# Top.net
KiCad netlist of a schematic drawn in Altium Designer
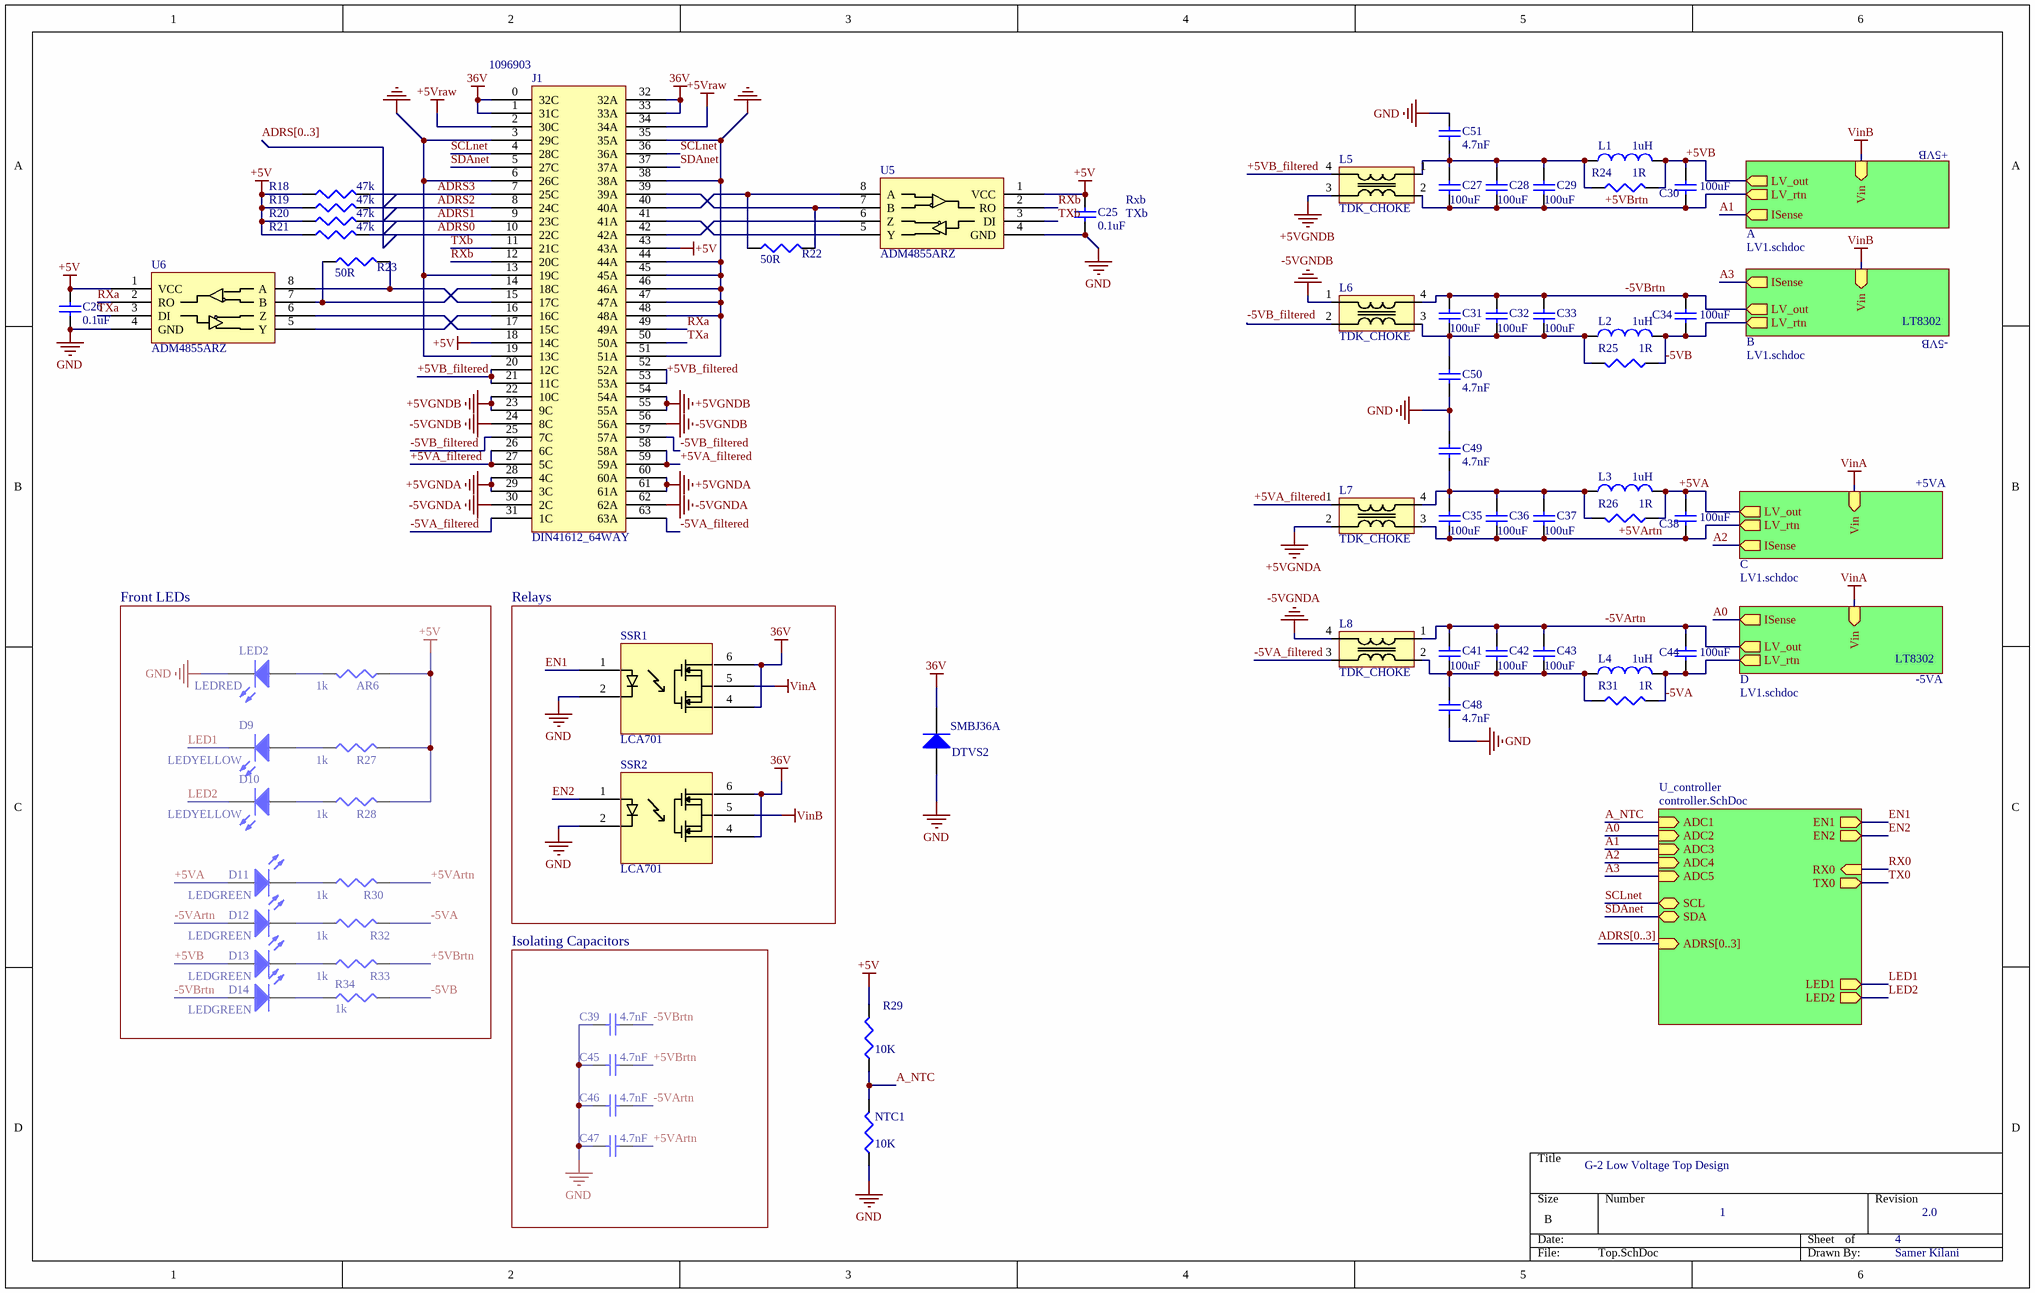
[diagram p0: Top.SchDoc]

(export (version "E")
  (design (tool "Eeschema 10.0.6"))
  (components
    (comp (ref "AR6")
      (value "1k")
      (footprint "J1-0603")
      (description "Resistor")
      (fields (field (name "PUBLISHER") "Altium Limited"))
      (libsource (lib "Miscellaneous Devices") (part "Res3"))
    )
    (comp (ref "C25")
      (value "0.1uF")
      (footprint "1608[0603]")
      (description "Capacitor (Semiconductor SIM Model)")
      (fields
        (field (name "PARTNO") "CC0603KRX7R9BB104")
        (field (name "Comment") "Cap Semi")
        (field (name "PUBLISHER") "Altium Limited")
      )
      (libsource (lib "Miscellaneous Devices") (part "Cap Semi"))
    )
    (comp (ref "C26")
      (value "0.1uF")
      (footprint "1608[0603]")
      (description "Capacitor (Semiconductor SIM Model)")
      (fields
        (field (name "PARTNO") "CC0603KRX7R9BB104")
        (field (name "Comment") "Cap Semi")
        (field (name "PUBLISHER") "Altium Limited")
      )
      (libsource (lib "Miscellaneous Devices") (part "Cap Semi"))
    )
    (comp (ref "C27")
      (value "100uF")
      (footprint "C1210")
      (description "Capacitor (Semiconductor SIM Model)")
      (fields
        (field (name "PARTNO") "CL32A107MPVNNNE")
        (field (name "Comment") "Cap Semi")
        (field (name "PUBLISHER") "Altium Limited")
      )
      (libsource (lib "Miscellaneous Devices") (part "Cap Semi"))
    )
    (comp (ref "C28")
      (value "100uF")
      (footprint "C1210")
      (description "Capacitor (Semiconductor SIM Model)")
      (fields
        (field (name "PARTNO") "CL32A107MPVNNNE")
        (field (name "Comment") "Cap Semi")
        (field (name "PUBLISHER") "Altium Limited")
      )
      (libsource (lib "Miscellaneous Devices") (part "Cap Semi"))
    )
    (comp (ref "C29")
      (value "100uF")
      (footprint "C1210")
      (description "Capacitor (Semiconductor SIM Model)")
      (fields
        (field (name "PARTNO") "CL32A107MPVNNNE")
        (field (name "Comment") "Cap Semi")
        (field (name "PUBLISHER") "Altium Limited")
      )
      (libsource (lib "Miscellaneous Devices") (part "Cap Semi"))
    )
    (comp (ref "C30")
      (value "100uF")
      (footprint "C1210")
      (description "Capacitor (Semiconductor SIM Model)")
      (fields
        (field (name "PARTNO") "C3225X5R0J107M250AC")
        (field (name "Comment") "Cap Semi")
        (field (name "PUBLISHER") "Altium Limited")
      )
      (libsource (lib "Miscellaneous Devices") (part "Cap Semi"))
    )
    (comp (ref "C31")
      (value "100uF")
      (footprint "C1210")
      (description "Capacitor (Semiconductor SIM Model)")
      (fields
        (field (name "PARTNO") "CL32A107MPVNNNE")
        (field (name "Comment") "Cap Semi")
        (field (name "PUBLISHER") "Altium Limited")
      )
      (libsource (lib "Miscellaneous Devices") (part "Cap Semi"))
    )
    (comp (ref "C32")
      (value "100uF")
      (footprint "C1210")
      (description "Capacitor (Semiconductor SIM Model)")
      (fields
        (field (name "PARTNO") "CL32A107MPVNNNE")
        (field (name "Comment") "Cap Semi")
        (field (name "PUBLISHER") "Altium Limited")
      )
      (libsource (lib "Miscellaneous Devices") (part "Cap Semi"))
    )
    (comp (ref "C33")
      (value "100uF")
      (footprint "C1210")
      (description "Capacitor (Semiconductor SIM Model)")
      (fields
        (field (name "PARTNO") "CL32A107MPVNNNE")
        (field (name "Comment") "Cap Semi")
        (field (name "PUBLISHER") "Altium Limited")
      )
      (libsource (lib "Miscellaneous Devices") (part "Cap Semi"))
    )
    (comp (ref "C34")
      (value "100uF")
      (footprint "C1210")
      (description "Capacitor (Semiconductor SIM Model)")
      (fields
        (field (name "PARTNO") "C3225X5R0J107M250AC")
        (field (name "Comment") "Cap Semi")
        (field (name "PUBLISHER") "Altium Limited")
      )
      (libsource (lib "Miscellaneous Devices") (part "Cap Semi"))
    )
    (comp (ref "C35")
      (value "100uF")
      (footprint "C1210")
      (description "Capacitor (Semiconductor SIM Model)")
      (fields
        (field (name "PARTNO") "CL32A107MPVNNNE")
        (field (name "Comment") "Cap Semi")
        (field (name "PUBLISHER") "Altium Limited")
      )
      (libsource (lib "Miscellaneous Devices") (part "Cap Semi"))
    )
    (comp (ref "C36")
      (value "100uF")
      (footprint "C1210")
      (description "Capacitor (Semiconductor SIM Model)")
      (fields
        (field (name "PARTNO") "CL32A107MPVNNNE")
        (field (name "Comment") "Cap Semi")
        (field (name "PUBLISHER") "Altium Limited")
      )
      (libsource (lib "Miscellaneous Devices") (part "Cap Semi"))
    )
    (comp (ref "C37")
      (value "100uF")
      (footprint "C1210")
      (description "Capacitor (Semiconductor SIM Model)")
      (fields
        (field (name "PARTNO") "CL32A107MPVNNNE")
        (field (name "Comment") "Cap Semi")
        (field (name "PUBLISHER") "Altium Limited")
      )
      (libsource (lib "Miscellaneous Devices") (part "Cap Semi"))
    )
    (comp (ref "C38")
      (value "100uF")
      (footprint "C1210")
      (description "Capacitor (Semiconductor SIM Model)")
      (fields
        (field (name "PARTNO") "C3225X5R0J107M250AC")
        (field (name "Comment") "Cap Semi")
        (field (name "PUBLISHER") "Altium Limited")
      )
      (libsource (lib "Miscellaneous Devices") (part "Cap Semi"))
    )
    (comp (ref "C39")
      (value "4.7nF")
      (footprint "1812")
      (description "Capacitor (Semiconductor SIM Model)")
      (fields
        (field (name "PARTNO") "C1812C472KDRACTU")
        (field (name "Comment") "Cap Semi")
        (field (name "PUBLISHER") "Altium Limited")
      )
      (libsource (lib "G2_LV") (part "Cap Semi"))
    )
    (comp (ref "C41")
      (value "100uF")
      (footprint "C1210")
      (description "Capacitor (Semiconductor SIM Model)")
      (fields
        (field (name "PARTNO") "CL32A107MPVNNNE")
        (field (name "Comment") "Cap Semi")
        (field (name "PUBLISHER") "Altium Limited")
      )
      (libsource (lib "Miscellaneous Devices") (part "Cap Semi"))
    )
    (comp (ref "C42")
      (value "100uF")
      (footprint "C1210")
      (description "Capacitor (Semiconductor SIM Model)")
      (fields
        (field (name "PARTNO") "CL32A107MPVNNNE")
        (field (name "Comment") "Cap Semi")
        (field (name "PUBLISHER") "Altium Limited")
      )
      (libsource (lib "Miscellaneous Devices") (part "Cap Semi"))
    )
    (comp (ref "C43")
      (value "100uF")
      (footprint "C1210")
      (description "Capacitor (Semiconductor SIM Model)")
      (fields
        (field (name "PARTNO") "CL32A107MPVNNNE")
        (field (name "Comment") "Cap Semi")
        (field (name "PUBLISHER") "Altium Limited")
      )
      (libsource (lib "Miscellaneous Devices") (part "Cap Semi"))
    )
    (comp (ref "C44")
      (value "100uF")
      (footprint "C1210")
      (description "Capacitor (Semiconductor SIM Model)")
      (fields
        (field (name "PARTNO") "C3225X5R0J107M250AC")
        (field (name "Comment") "Cap Semi")
        (field (name "PUBLISHER") "Altium Limited")
      )
      (libsource (lib "Miscellaneous Devices") (part "Cap Semi"))
    )
    (comp (ref "C45")
      (value "4.7nF")
      (footprint "1812")
      (description "Capacitor (Semiconductor SIM Model)")
      (fields
        (field (name "PARTNO") "C1812C472KDRACTU")
        (field (name "Comment") "Cap Semi")
        (field (name "PUBLISHER") "Altium Limited")
      )
      (libsource (lib "G2_LV") (part "Cap Semi"))
    )
    (comp (ref "C46")
      (value "4.7nF")
      (footprint "1812")
      (description "Capacitor (Semiconductor SIM Model)")
      (fields
        (field (name "PARTNO") "C1812C472KDRACTU")
        (field (name "Comment") "Cap Semi")
        (field (name "PUBLISHER") "Altium Limited")
      )
      (libsource (lib "G2_LV") (part "Cap Semi"))
    )
    (comp (ref "C47")
      (value "4.7nF")
      (footprint "1812")
      (description "Capacitor (Semiconductor SIM Model)")
      (fields
        (field (name "PARTNO") "C1812C472KDRACTU")
        (field (name "Comment") "Cap Semi")
        (field (name "PUBLISHER") "Altium Limited")
      )
      (libsource (lib "G2_LV") (part "Cap Semi"))
    )
    (comp (ref "C48")
      (value "4.7nF")
      (footprint "1812")
      (description "Capacitor (Semiconductor SIM Model)")
      (fields
        (field (name "PARTNO") "C1812C472KDRACTU")
        (field (name "Comment") "Cap Semi")
        (field (name "PUBLISHER") "Altium Limited")
      )
      (libsource (lib "G2_LV") (part "Cap Semi"))
    )
    (comp (ref "C49")
      (value "4.7nF")
      (footprint "1812")
      (description "Capacitor (Semiconductor SIM Model)")
      (fields
        (field (name "PARTNO") "C1812C472KDRACTU")
        (field (name "Comment") "Cap Semi")
        (field (name "PUBLISHER") "Altium Limited")
      )
      (libsource (lib "G2_LV") (part "Cap Semi"))
    )
    (comp (ref "C50")
      (value "4.7nF")
      (footprint "1812")
      (description "Capacitor (Semiconductor SIM Model)")
      (fields
        (field (name "PARTNO") "C1812C472KDRACTU")
        (field (name "Comment") "Cap Semi")
        (field (name "PUBLISHER") "Altium Limited")
      )
      (libsource (lib "G2_LV") (part "Cap Semi"))
    )
    (comp (ref "C51")
      (value "4.7nF")
      (footprint "1812")
      (description "Capacitor (Semiconductor SIM Model)")
      (fields
        (field (name "PARTNO") "C1812C472KDRACTU")
        (field (name "Comment") "Cap Semi")
        (field (name "PUBLISHER") "Altium Limited")
      )
      (libsource (lib "G2_LV") (part "Cap Semi"))
    )
    (comp (ref "D9")
      (value "LEDYELLOW")
      (footprint "LEDYELLOW")
      (fields (field (name "PARTNO") "550-0307F"))
      (libsource (lib "G2_LV") (part "LEDYELLOW"))
    )
    (comp (ref "D10")
      (value "LEDYELLOW")
      (footprint "LEDYELLOW")
      (fields (field (name "PARTNO") "550-0307F"))
      (libsource (lib "G2_LV") (part "LEDYELLOW"))
    )
    (comp (ref "D11")
      (value "LEDGREEN")
      (footprint "LEDGREEN")
      (fields (field (name "PARTNO") "550-0207F"))
      (libsource (lib "G2_LV") (part "LEDGREEN"))
    )
    (comp (ref "D12")
      (value "LEDGREEN")
      (footprint "LEDGREEN")
      (fields (field (name "PARTNO") "550-0207F"))
      (libsource (lib "G2_LV") (part "LEDGREEN"))
    )
    (comp (ref "D13")
      (value "LEDGREEN")
      (footprint "LEDGREEN")
      (fields (field (name "PARTNO") "550-0207F"))
      (libsource (lib "G2_LV") (part "LEDGREEN"))
    )
    (comp (ref "D14")
      (value "LEDGREEN")
      (footprint "LEDGREEN")
      (fields (field (name "PARTNO") "550-0207F"))
      (libsource (lib "G2_LV") (part "LEDGREEN"))
    )
    (comp (ref "DTVS2")
      (value "SMBJ48A")
      (footprint "SMBJ")
      (description "TVS")
      (fields (field (name "PARTNO") "SMBJ36A") (field (name "PUBLISHER") "Altium Limited"))
      (libsource (lib "G2_LV") (part "SMBJ"))
    )
    (comp (ref "J1")
      (value "DIN41612_64WAY")
      (footprint "09 03 164 6919")
      (fields (field (name "PARTNO") "0903 164 6921") (field (name "SUPPLIER PART NUMBER 1") "1096903"))
      (libsource (lib "G2_LV") (part "DIN41612_64WAY"))
    )
    (comp (ref "L1")
      (value "1uH")
      (footprint "MPLC0730")
      (description "Inductor")
      (fields (field (name "PARTNO") "MPLC0730L1R0") (field (name "PUBLISHER") "Altium Limited"))
      (libsource (lib "G2_LV") (part "Inductor"))
    )
    (comp (ref "L2")
      (value "1uH")
      (footprint "MPLC0730")
      (description "Inductor")
      (fields (field (name "PARTNO") "MPLC0730L1R0") (field (name "PUBLISHER") "Altium Limited"))
      (libsource (lib "G2_LV") (part "Inductor"))
    )
    (comp (ref "L3")
      (value "1uH")
      (footprint "MPLC0730")
      (description "Inductor")
      (fields (field (name "PARTNO") "MPLC0730L1R0") (field (name "PUBLISHER") "Altium Limited"))
      (libsource (lib "G2_LV") (part "Inductor"))
    )
    (comp (ref "L4")
      (value "1uH")
      (footprint "MPLC0730")
      (description "Inductor")
      (fields (field (name "PARTNO") "MPLC0730L1R0") (field (name "PUBLISHER") "Altium Limited"))
      (libsource (lib "G2_LV") (part "Inductor"))
    )
    (comp (ref "L5")
      (value "TDK_CHOKE")
      (footprint "ACMV_TDK")
      (fields (field (name "PARTNO") "ACM90V-701-2PL"))
      (libsource (lib "") (part "TDK_CHOKE_1"))
    )
    (comp (ref "L6")
      (value "TDK_CHOKE")
      (footprint "ACMV_TDK")
      (fields (field (name "PARTNO") "ACM90V-701-2PL"))
      (libsource (lib "G2_LV") (part "TDK_CHOKE"))
    )
    (comp (ref "L7")
      (value "TDK_CHOKE")
      (footprint "ACMV_TDK")
      (fields (field (name "PARTNO") "ACM90V-701-2PL"))
      (libsource (lib "G2_LV") (part "TDK_CHOKE"))
    )
    (comp (ref "L8")
      (value "TDK_CHOKE")
      (footprint "ACMV_TDK")
      (fields (field (name "PARTNO") "ACM90V-701-2PL"))
      (libsource (lib "") (part "TDK_CHOKE_1"))
    )
    (comp (ref "LED2")
      (value "LEDRED")
      (footprint "LEDRED")
      (fields (field (name "PARTNO") "550-0407F"))
      (libsource (lib "G2_LV") (part "LEDRED"))
    )
    (comp (ref "NTC1")
      (value "10K")
      (footprint "J1-0603")
      (description "Resistor")
      (fields (field (name "PARTNO") "NCP18XH103J03RB") (field (name "PUBLISHER") "Altium Limited"))
      (libsource (lib "Miscellaneous Devices") (part "Res3"))
    )
    (comp (ref "R18")
      (value "47k")
      (footprint "J1-0603")
      (description "Resistor")
      (fields (field (name "Comment") "Res3") (field (name "PUBLISHER") "Altium Limited"))
      (libsource (lib "Miscellaneous Devices") (part "Res3"))
    )
    (comp (ref "R19")
      (value "47k")
      (footprint "J1-0603")
      (description "Resistor")
      (fields (field (name "Comment") "Res3") (field (name "PUBLISHER") "Altium Limited"))
      (libsource (lib "Miscellaneous Devices") (part "Res3"))
    )
    (comp (ref "R20")
      (value "47k")
      (footprint "J1-0603")
      (description "Resistor")
      (fields (field (name "Comment") "Res3") (field (name "PUBLISHER") "Altium Limited"))
      (libsource (lib "Miscellaneous Devices") (part "Res3"))
    )
    (comp (ref "R21")
      (value "47k")
      (footprint "J1-0603")
      (description "Resistor")
      (fields (field (name "Comment") "Res3") (field (name "PUBLISHER") "Altium Limited"))
      (libsource (lib "Miscellaneous Devices") (part "Res3"))
    )
    (comp (ref "R22")
      (value "50R")
      (footprint "J1-0603")
      (description "Resistor")
      (fields (field (name "PUBLISHER") "Altium Limited"))
      (libsource (lib "Miscellaneous Devices") (part "Res3"))
    )
    (comp (ref "R23")
      (value "50R")
      (footprint "J1-0603")
      (description "Resistor")
      (fields (field (name "PUBLISHER") "Altium Limited"))
      (libsource (lib "Miscellaneous Devices") (part "Res3"))
    )
    (comp (ref "R24")
      (value "1R")
      (footprint "J1-0603")
      (description "Resistor")
      (fields (field (name "Comment") "Res3") (field (name "PUBLISHER") "Altium Limited"))
      (libsource (lib "Miscellaneous Devices") (part "Res3"))
    )
    (comp (ref "R25")
      (value "1R")
      (footprint "J1-0603")
      (description "Resistor")
      (fields (field (name "Comment") "Res3") (field (name "PUBLISHER") "Altium Limited"))
      (libsource (lib "Miscellaneous Devices") (part "Res3"))
    )
    (comp (ref "R26")
      (value "1R")
      (footprint "J1-0603")
      (description "Resistor")
      (fields (field (name "Comment") "Res3") (field (name "PUBLISHER") "Altium Limited"))
      (libsource (lib "Miscellaneous Devices") (part "Res3"))
    )
    (comp (ref "R27")
      (value "1k")
      (footprint "J1-0603")
      (description "Resistor")
      (fields (field (name "Comment") "Res3") (field (name "PUBLISHER") "Altium Limited"))
      (libsource (lib "Miscellaneous Devices") (part "Res3"))
    )
    (comp (ref "R28")
      (value "1k")
      (footprint "J1-0603")
      (description "Resistor")
      (fields (field (name "Comment") "Res3") (field (name "PUBLISHER") "Altium Limited"))
      (libsource (lib "Miscellaneous Devices") (part "Res3"))
    )
    (comp (ref "R29")
      (value "10K")
      (footprint "J1-0603")
      (description "Resistor")
      (fields (field (name "PUBLISHER") "Altium Limited"))
      (libsource (lib "Miscellaneous Devices") (part "Res3"))
    )
    (comp (ref "R30")
      (value "1k")
      (footprint "J1-0603")
      (description "Resistor")
      (fields (field (name "Comment") "Res3") (field (name "PUBLISHER") "Altium Limited"))
      (libsource (lib "Miscellaneous Devices") (part "Res3"))
    )
    (comp (ref "R31")
      (value "1R")
      (footprint "J1-0603")
      (description "Resistor")
      (fields (field (name "Comment") "Res3") (field (name "PUBLISHER") "Altium Limited"))
      (libsource (lib "Miscellaneous Devices") (part "Res3"))
    )
    (comp (ref "R32")
      (value "1k")
      (footprint "J1-0603")
      (description "Resistor")
      (fields (field (name "Comment") "Res3") (field (name "PUBLISHER") "Altium Limited"))
      (libsource (lib "Miscellaneous Devices") (part "Res3"))
    )
    (comp (ref "R33")
      (value "1k")
      (footprint "J1-0603")
      (description "Resistor")
      (fields (field (name "Comment") "Res3") (field (name "PUBLISHER") "Altium Limited"))
      (libsource (lib "Miscellaneous Devices") (part "Res3"))
    )
    (comp (ref "R34")
      (value "1k")
      (footprint "J1-0603")
      (description "Resistor")
      (fields (field (name "Comment") "Res3") (field (name "PUBLISHER") "Altium Limited"))
      (libsource (lib "Miscellaneous Devices") (part "Res3"))
    )
    (comp (ref "SSR1")
      (value "LCA701")
      (footprint "LCA701S")
      (fields (field (name "PARTNO") "LCA701S"))
      (libsource (lib "G2_LV") (part "LCA701"))
    )
    (comp (ref "SSR2")
      (value "LCA701")
      (footprint "LCA701S")
      (fields (field (name "PARTNO") "LCA701S"))
      (libsource (lib "G2_LV") (part "LCA701"))
    )
    (comp (ref "U5")
      (value "ADM4855ARZ")
      (footprint "SOICN8")
      (libsource (lib "BACKPLANElib") (part "SP3084EEN-L"))
    )
    (comp (ref "U6") (value "ADM4855ARZ") (footprint "SOICN8") (libsource (lib "") (part "SP3084EEN-L_1")))
  )
  (nets
    (net (code "1") (name "+5V") (class "Default")
      (node (ref "AR6") (pin "1") (pinfunction "1_1") (pintype "passive"))
      (node (ref "C25") (pin "2") (pinfunction "2_2") (pintype "passive"))
      (node (ref "C26") (pin "2") (pinfunction "2_2") (pintype "passive"))
      (node (ref "J1") (pin "18") (pinfunction "14C_18") (pintype "passive"))
      (node (ref "J1") (pin "43") (pinfunction "43A_43") (pintype "passive"))
      (node (ref "R18") (pin "1") (pinfunction "1_1") (pintype "passive"))
      (node (ref "R19") (pin "1") (pinfunction "1_1") (pintype "passive"))
      (node (ref "R20") (pin "1") (pinfunction "1_1") (pintype "passive"))
      (node (ref "R21") (pin "1") (pinfunction "1_1") (pintype "passive"))
      (node (ref "R27") (pin "2") (pinfunction "2_2") (pintype "passive"))
      (node (ref "R28") (pin "2") (pinfunction "2_2") (pintype "passive"))
      (node (ref "R29") (pin "2") (pinfunction "2_2") (pintype "passive"))
      (node (ref "U5") (pin "1") (pinfunction "VCC_1") (pintype "passive"))
      (node (ref "U6") (pin "1") (pinfunction "VCC_1") (pintype "passive"))
    )
    (net (code "2") (name "+5VGNDA") (class "Default")
      (node (ref "J1") (pin "28") (pinfunction "4C_28") (pintype "passive"))
      (node (ref "J1") (pin "29") (pinfunction "3C_29") (pintype "passive"))
      (node (ref "J1") (pin "60") (pinfunction "60A_60") (pintype "passive"))
      (node (ref "J1") (pin "61") (pinfunction "61A_61") (pintype "passive"))
      (node (ref "L7") (pin "2") (pinfunction "2_2") (pintype "passive"))
    )
    (net (code "3") (name "+5VGNDB") (class "Default")
      (node (ref "J1") (pin "22") (pinfunction "10C_22") (pintype "passive"))
      (node (ref "J1") (pin "23") (pinfunction "9C_23") (pintype "passive"))
      (node (ref "J1") (pin "54") (pinfunction "54A_54") (pintype "passive"))
      (node (ref "J1") (pin "55") (pinfunction "55A_55") (pintype "passive"))
      (node (ref "L5") (pin "3") (pinfunction "3_3") (pintype "passive"))
    )
    (net (code "4") (name "+5Vraw") (class "Default")
      (node (ref "J1") (pin "2") (pinfunction "30C_2") (pintype "passive"))
      (node (ref "J1") (pin "34") (pinfunction "34A_34") (pintype "passive"))
    )
    (net (code "5") (name "-5VGNDA") (class "Default")
      (node (ref "J1") (pin "30") (pinfunction "2C_30") (pintype "passive"))
      (node (ref "J1") (pin "62") (pinfunction "62A_62") (pintype "passive"))
      (node (ref "L8") (pin "4") (pinfunction "4_4") (pintype "passive"))
    )
    (net (code "6") (name "-5VGNDB") (class "Default")
      (node (ref "J1") (pin "24") (pinfunction "8C_24") (pintype "passive"))
      (node (ref "J1") (pin "56") (pinfunction "56A_56") (pintype "passive"))
      (node (ref "L6") (pin "1") (pinfunction "1_1") (pintype "passive"))
    )
    (net (code "7") (name "/+5VA") (class "Default")
      (node (ref "C38") (pin "1") (pinfunction "1_1") (pintype "passive"))
      (node (ref "D11") (pin "2") (pinfunction "A_2") (pintype "passive"))
      (node (ref "L3") (pin "2") (pinfunction "2_2") (pintype "passive"))
      (node (ref "R26") (pin "1") (pinfunction "1_1") (pintype "passive"))
    )
    (net (code "8") (name "/+5VA_filtered") (class "Default")
      (node (ref "J1") (pin "26") (pinfunction "6C_26") (pintype "passive"))
      (node (ref "J1") (pin "27") (pinfunction "5C_27") (pintype "passive"))
      (node (ref "J1") (pin "58") (pinfunction "58A_58") (pintype "passive"))
      (node (ref "J1") (pin "59") (pinfunction "59A_59") (pintype "passive"))
      (node (ref "L7") (pin "1") (pinfunction "1_1") (pintype "passive"))
    )
    (net (code "9") (name "/+5VArtn") (class "Default")
      (node (ref "C35") (pin "2") (pinfunction "2_2") (pintype "passive"))
      (node (ref "C36") (pin "2") (pinfunction "2_2") (pintype "passive"))
      (node (ref "C37") (pin "2") (pinfunction "2_2") (pintype "passive"))
      (node (ref "C38") (pin "2") (pinfunction "2_2") (pintype "passive"))
      (node (ref "C47") (pin "2") (pinfunction "2_2") (pintype "passive"))
      (node (ref "L7") (pin "3") (pinfunction "3_3") (pintype "passive"))
      (node (ref "R30") (pin "2") (pinfunction "2_2") (pintype "passive"))
    )
    (net (code "10") (name "/+5VB") (class "Default")
      (node (ref "C30") (pin "2") (pinfunction "2_2") (pintype "passive"))
      (node (ref "D13") (pin "2") (pinfunction "A_2") (pintype "passive"))
      (node (ref "L1") (pin "2") (pinfunction "2_2") (pintype "passive"))
      (node (ref "R24") (pin "2") (pinfunction "2_2") (pintype "passive"))
    )
    (net (code "11") (name "/+5VB_filtered") (class "Default")
      (node (ref "J1") (pin "20") (pinfunction "12C_20") (pintype "passive"))
      (node (ref "J1") (pin "21") (pinfunction "11C_21") (pintype "passive"))
      (node (ref "J1") (pin "52") (pinfunction "52A_52") (pintype "passive"))
      (node (ref "J1") (pin "53") (pinfunction "53A_53") (pintype "passive"))
      (node (ref "L5") (pin "4") (pinfunction "4_4") (pintype "passive"))
    )
    (net (code "12") (name "/+5VBrtn") (class "Default")
      (node (ref "C27") (pin "1") (pinfunction "1_1") (pintype "passive"))
      (node (ref "C28") (pin "1") (pinfunction "1_1") (pintype "passive"))
      (node (ref "C29") (pin "1") (pinfunction "1_1") (pintype "passive"))
      (node (ref "C30") (pin "1") (pinfunction "1_1") (pintype "passive"))
      (node (ref "C45") (pin "2") (pinfunction "2_2") (pintype "passive"))
      (node (ref "L5") (pin "2") (pinfunction "2_2") (pintype "passive"))
      (node (ref "R33") (pin "2") (pinfunction "2_2") (pintype "passive"))
    )
    (net (code "13") (name "/-5VA") (class "Default")
      (node (ref "C44") (pin "1") (pinfunction "1_1") (pintype "passive"))
      (node (ref "L4") (pin "2") (pinfunction "2_2") (pintype "passive"))
      (node (ref "R31") (pin "2") (pinfunction "2_2") (pintype "passive"))
      (node (ref "R32") (pin "2") (pinfunction "2_2") (pintype "passive"))
    )
    (net (code "14") (name "/-5VA_filtered") (class "Default")
      (node (ref "J1") (pin "31") (pinfunction "1C_31") (pintype "passive"))
      (node (ref "J1") (pin "63") (pinfunction "63A_63") (pintype "passive"))
      (node (ref "L8") (pin "3") (pinfunction "3_3") (pintype "passive"))
    )
    (net (code "15") (name "/-5VArtn") (class "Default")
      (node (ref "C41") (pin "2") (pinfunction "2_2") (pintype "passive"))
      (node (ref "C42") (pin "2") (pinfunction "2_2") (pintype "passive"))
      (node (ref "C43") (pin "2") (pinfunction "2_2") (pintype "passive"))
      (node (ref "C44") (pin "2") (pinfunction "2_2") (pintype "passive"))
      (node (ref "C46") (pin "2") (pinfunction "2_2") (pintype "passive"))
      (node (ref "D12") (pin "2") (pinfunction "A_2") (pintype "passive"))
      (node (ref "L8") (pin "1") (pinfunction "1_1") (pintype "passive"))
    )
    (net (code "16") (name "/-5VB") (class "Default")
      (node (ref "C34") (pin "2") (pinfunction "2_2") (pintype "passive"))
      (node (ref "L2") (pin "2") (pinfunction "2_2") (pintype "passive"))
      (node (ref "R25") (pin "1") (pinfunction "1_1") (pintype "passive"))
      (node (ref "R34") (pin "2") (pinfunction "2_2") (pintype "passive"))
    )
    (net (code "17") (name "/-5VB_filtered") (class "Default")
      (node (ref "J1") (pin "25") (pinfunction "7C_25") (pintype "passive"))
      (node (ref "J1") (pin "57") (pinfunction "57A_57") (pintype "passive"))
      (node (ref "L6") (pin "2") (pinfunction "2_2") (pintype "passive"))
    )
    (net (code "18") (name "/-5VBrtn") (class "Default")
      (node (ref "C31") (pin "1") (pinfunction "1_1") (pintype "passive"))
      (node (ref "C32") (pin "1") (pinfunction "1_1") (pintype "passive"))
      (node (ref "C33") (pin "1") (pinfunction "1_1") (pintype "passive"))
      (node (ref "C34") (pin "1") (pinfunction "1_1") (pintype "passive"))
      (node (ref "C39") (pin "2") (pinfunction "2_2") (pintype "passive"))
      (node (ref "D14") (pin "2") (pinfunction "A_2") (pintype "passive"))
      (node (ref "L6") (pin "4") (pinfunction "4_4") (pintype "passive"))
    )
    (net (code "23") (name "/ADRS0") (class "Default")
      (node (ref "J1") (pin "10") (pinfunction "22C_10") (pintype "passive"))
      (node (ref "R21") (pin "2") (pinfunction "2_2") (pintype "passive"))
    )
    (net (code "24") (name "/ADRS1") (class "Default")
      (node (ref "J1") (pin "9") (pinfunction "23C_9") (pintype "passive"))
      (node (ref "R20") (pin "2") (pinfunction "2_2") (pintype "passive"))
    )
    (net (code "25") (name "/ADRS2") (class "Default")
      (node (ref "J1") (pin "8") (pinfunction "24C_8") (pintype "passive"))
      (node (ref "R19") (pin "2") (pinfunction "2_2") (pintype "passive"))
    )
    (net (code "26") (name "/ADRS3") (class "Default")
      (node (ref "J1") (pin "7") (pinfunction "25C_7") (pintype "passive"))
      (node (ref "R18") (pin "2") (pinfunction "2_2") (pintype "passive"))
    )
    (net (code "28") (name "/A_NTC") (class "Default")
      (node (ref "NTC1") (pin "2") (pinfunction "2_2") (pintype "passive"))
      (node (ref "R29") (pin "1") (pinfunction "1_1") (pintype "passive"))
    )
    (net (code "29") (name "/EN1") (class "Default")
      (node (ref "SSR1") (pin "1") (pinfunction "1_1") (pintype "passive"))
    )
    (net (code "30") (name "/EN2") (class "Default")
      (node (ref "SSR2") (pin "1") (pinfunction "1_1") (pintype "passive"))
    )
    (net (code "31") (name "/LED1") (class "Default")
      (node (ref "D9") (pin "1") (pinfunction "K_1") (pintype "passive"))
    )
    (net (code "32") (name "/LED2") (class "Default")
      (node (ref "D10") (pin "1") (pinfunction "K_1") (pintype "passive"))
    )
    (net (code "34") (name "/RXa") (class "Default")
      (node (ref "J1") (pin "49") (pinfunction "49A_49") (pintype "passive"))
      (node (ref "U6") (pin "2") (pinfunction "RO_2") (pintype "passive"))
    )
    (net (code "35") (name "/RXb") (class "Default")
      (node (ref "J1") (pin "12") (pinfunction "20C_12") (pintype "passive"))
      (node (ref "U5") (pin "2") (pinfunction "RO_2") (pintype "passive"))
    )
    (net (code "36") (name "/SCLnet") (class "Default")
      (node (ref "J1") (pin "36") (pinfunction "36A_36") (pintype "passive"))
      (node (ref "J1") (pin "4") (pinfunction "28C_4") (pintype "passive"))
    )
    (net (code "37") (name "/SDAnet") (class "Default")
      (node (ref "J1") (pin "37") (pinfunction "37A_37") (pintype "passive"))
      (node (ref "J1") (pin "5") (pinfunction "27C_5") (pintype "passive"))
    )
    (net (code "39") (name "/TXa") (class "Default")
      (node (ref "J1") (pin "50") (pinfunction "50A_50") (pintype "passive"))
      (node (ref "U6") (pin "3") (pinfunction "DI_3") (pintype "passive"))
    )
    (net (code "40") (name "/TXb") (class "Default")
      (node (ref "J1") (pin "11") (pinfunction "21C_11") (pintype "passive"))
      (node (ref "U5") (pin "3") (pinfunction "DI_3") (pintype "passive"))
    )
    (net (code "41") (name "36V") (class "Default")
      (node (ref "DTVS2") (pin "1") (pinfunction "K_1") (pintype "passive"))
      (node (ref "J1") (pin "0") (pinfunction "32C_0") (pintype "passive"))
      (node (ref "J1") (pin "1") (pinfunction "31C_1") (pintype "passive"))
      (node (ref "J1") (pin "32") (pinfunction "32A_32") (pintype "passive"))
      (node (ref "J1") (pin "33") (pinfunction "33A_33") (pintype "passive"))
      (node (ref "SSR1") (pin "4") (pinfunction "4_4") (pintype "passive"))
      (node (ref "SSR1") (pin "6") (pinfunction "6_6") (pintype "passive"))
      (node (ref "SSR2") (pin "4") (pinfunction "4_4") (pintype "passive"))
      (node (ref "SSR2") (pin "6") (pinfunction "6_6") (pintype "passive"))
    )
    (net (code "42") (name "GND") (class "Default")
      (node (ref "C25") (pin "1") (pinfunction "1_1") (pintype "passive"))
      (node (ref "C26") (pin "1") (pinfunction "1_1") (pintype "passive"))
      (node (ref "C39") (pin "1") (pinfunction "1_1") (pintype "passive"))
      (node (ref "C45") (pin "1") (pinfunction "1_1") (pintype "passive"))
      (node (ref "C46") (pin "1") (pinfunction "1_1") (pintype "passive"))
      (node (ref "C47") (pin "1") (pinfunction "1_1") (pintype "passive"))
      (node (ref "C48") (pin "1") (pinfunction "1_1") (pintype "passive"))
      (node (ref "C49") (pin "2") (pinfunction "2_2") (pintype "passive"))
      (node (ref "C50") (pin "1") (pinfunction "1_1") (pintype "passive"))
      (node (ref "C51") (pin "2") (pinfunction "2_2") (pintype "passive"))
      (node (ref "DTVS2") (pin "2") (pinfunction "A_2") (pintype "passive"))
      (node (ref "J1") (pin "13") (pinfunction "19C_13") (pintype "passive"))
      (node (ref "J1") (pin "19") (pinfunction "13C_19") (pintype "passive"))
      (node (ref "J1") (pin "3") (pinfunction "29C_3") (pintype "passive"))
      (node (ref "J1") (pin "35") (pinfunction "35A_35") (pintype "passive"))
      (node (ref "J1") (pin "38") (pinfunction "38A_38") (pintype "passive"))
      (node (ref "J1") (pin "44") (pinfunction "44A_44") (pintype "passive"))
      (node (ref "J1") (pin "45") (pinfunction "45A_45") (pintype "passive"))
      (node (ref "J1") (pin "46") (pinfunction "46A_46") (pintype "passive"))
      (node (ref "J1") (pin "47") (pinfunction "47A_47") (pintype "passive"))
      (node (ref "J1") (pin "48") (pinfunction "48A_48") (pintype "passive"))
      (node (ref "J1") (pin "51") (pinfunction "51A_51") (pintype "passive"))
      (node (ref "J1") (pin "6") (pinfunction "26C_6") (pintype "passive"))
      (node (ref "LED2") (pin "1") (pinfunction "K_1") (pintype "passive"))
      (node (ref "NTC1") (pin "1") (pinfunction "1_1") (pintype "passive"))
      (node (ref "SSR1") (pin "2") (pinfunction "2_2") (pintype "passive"))
      (node (ref "SSR2") (pin "2") (pinfunction "2_2") (pintype "passive"))
      (node (ref "U5") (pin "4") (pinfunction "GND_4") (pintype "passive"))
      (node (ref "U6") (pin "4") (pinfunction "GND_4") (pintype "passive"))
    )
    (net (code "43") (name "Net-(C27-Pad2)") (class "Default")
      (node (ref "C27") (pin "2") (pinfunction "2_2") (pintype "passive"))
      (node (ref "C28") (pin "2") (pinfunction "2_2") (pintype "passive"))
      (node (ref "C29") (pin "2") (pinfunction "2_2") (pintype "passive"))
      (node (ref "C51") (pin "1") (pinfunction "1_1") (pintype "passive"))
      (node (ref "L1") (pin "1") (pinfunction "1_1") (pintype "passive"))
      (node (ref "L5") (pin "1") (pinfunction "1_1") (pintype "passive"))
      (node (ref "R24") (pin "1") (pinfunction "1_1") (pintype "passive"))
    )
    (net (code "44") (name "Net-(C31-Pad2)") (class "Default")
      (node (ref "C31") (pin "2") (pinfunction "2_2") (pintype "passive"))
      (node (ref "C32") (pin "2") (pinfunction "2_2") (pintype "passive"))
      (node (ref "C33") (pin "2") (pinfunction "2_2") (pintype "passive"))
      (node (ref "C50") (pin "2") (pinfunction "2_2") (pintype "passive"))
      (node (ref "L2") (pin "1") (pinfunction "1_1") (pintype "passive"))
      (node (ref "L6") (pin "3") (pinfunction "3_3") (pintype "passive"))
      (node (ref "R25") (pin "2") (pinfunction "2_2") (pintype "passive"))
    )
    (net (code "45") (name "Net-(C35-Pad1)") (class "Default")
      (node (ref "C35") (pin "1") (pinfunction "1_1") (pintype "passive"))
      (node (ref "C36") (pin "1") (pinfunction "1_1") (pintype "passive"))
      (node (ref "C37") (pin "1") (pinfunction "1_1") (pintype "passive"))
      (node (ref "C49") (pin "1") (pinfunction "1_1") (pintype "passive"))
      (node (ref "L3") (pin "1") (pinfunction "1_1") (pintype "passive"))
      (node (ref "L7") (pin "4") (pinfunction "4_4") (pintype "passive"))
      (node (ref "R26") (pin "2") (pinfunction "2_2") (pintype "passive"))
    )
    (net (code "46") (name "Net-(C41-Pad1)") (class "Default")
      (node (ref "C41") (pin "1") (pinfunction "1_1") (pintype "passive"))
      (node (ref "C42") (pin "1") (pinfunction "1_1") (pintype "passive"))
      (node (ref "C43") (pin "1") (pinfunction "1_1") (pintype "passive"))
      (node (ref "C48") (pin "2") (pinfunction "2_2") (pintype "passive"))
      (node (ref "L4") (pin "1") (pinfunction "1_1") (pintype "passive"))
      (node (ref "L8") (pin "2") (pinfunction "2_2") (pintype "passive"))
      (node (ref "R31") (pin "1") (pinfunction "1_1") (pintype "passive"))
    )
    (net (code "47") (name "Net-(D9-A)") (class "Default")
      (node (ref "D9") (pin "2") (pinfunction "A_2") (pintype "passive"))
      (node (ref "R27") (pin "1") (pinfunction "1_1") (pintype "passive"))
    )
    (net (code "48") (name "Net-(D10-A)") (class "Default")
      (node (ref "D10") (pin "2") (pinfunction "A_2") (pintype "passive"))
      (node (ref "R28") (pin "1") (pinfunction "1_1") (pintype "passive"))
    )
    (net (code "49") (name "Net-(D11-K)") (class "Default")
      (node (ref "D11") (pin "1") (pinfunction "K_1") (pintype "passive"))
      (node (ref "R30") (pin "1") (pinfunction "1_1") (pintype "passive"))
    )
    (net (code "50") (name "Net-(D12-K)") (class "Default")
      (node (ref "D12") (pin "1") (pinfunction "K_1") (pintype "passive"))
      (node (ref "R32") (pin "1") (pinfunction "1_1") (pintype "passive"))
    )
    (net (code "51") (name "Net-(D13-K)") (class "Default")
      (node (ref "D13") (pin "1") (pinfunction "K_1") (pintype "passive"))
      (node (ref "R33") (pin "1") (pinfunction "1_1") (pintype "passive"))
    )
    (net (code "52") (name "Net-(D14-K)") (class "Default")
      (node (ref "D14") (pin "1") (pinfunction "K_1") (pintype "passive"))
      (node (ref "R34") (pin "1") (pinfunction "1_1") (pintype "passive"))
    )
    (net (code "53") (name "Net-(J1-15C)") (class "Default")
      (node (ref "J1") (pin "17") (pinfunction "15C_17") (pintype "passive"))
      (node (ref "U6") (pin "6") (pinfunction "Z_6") (pintype "passive"))
    )
    (net (code "54") (name "Net-(J1-16C)") (class "Default")
      (node (ref "J1") (pin "16") (pinfunction "16C_16") (pintype "passive"))
      (node (ref "U6") (pin "5") (pinfunction "Y_5") (pintype "passive"))
    )
    (net (code "55") (name "Net-(J1-17C)") (class "Default")
      (node (ref "J1") (pin "15") (pinfunction "17C_15") (pintype "passive"))
      (node (ref "R23") (pin "2") (pinfunction "2_2") (pintype "passive"))
      (node (ref "U6") (pin "8") (pinfunction "A_8") (pintype "passive"))
    )
    (net (code "56") (name "Net-(J1-18C)") (class "Default")
      (node (ref "J1") (pin "14") (pinfunction "18C_14") (pintype "passive"))
      (node (ref "R23") (pin "1") (pinfunction "1_1") (pintype "passive"))
      (node (ref "U6") (pin "7") (pinfunction "B_7") (pintype "passive"))
    )
    (net (code "57") (name "Net-(J1-39A)") (class "Default")
      (node (ref "J1") (pin "39") (pinfunction "39A_39") (pintype "passive"))
      (node (ref "R22") (pin "2") (pinfunction "2_2") (pintype "passive"))
      (node (ref "U5") (pin "7") (pinfunction "B_7") (pintype "passive"))
    )
    (net (code "58") (name "Net-(J1-40A)") (class "Default")
      (node (ref "J1") (pin "40") (pinfunction "40A_40") (pintype "passive"))
      (node (ref "R22") (pin "1") (pinfunction "1_1") (pintype "passive"))
      (node (ref "U5") (pin "8") (pinfunction "A_8") (pintype "passive"))
    )
    (net (code "59") (name "Net-(J1-41A)") (class "Default")
      (node (ref "J1") (pin "41") (pinfunction "41A_41") (pintype "passive"))
      (node (ref "U5") (pin "5") (pinfunction "Y_5") (pintype "passive"))
    )
    (net (code "60") (name "Net-(J1-42A)") (class "Default")
      (node (ref "J1") (pin "42") (pinfunction "42A_42") (pintype "passive"))
      (node (ref "U5") (pin "6") (pinfunction "Z_6") (pintype "passive"))
    )
    (net (code "61") (name "Net-(LED2-A)") (class "Default")
      (node (ref "AR6") (pin "2") (pinfunction "2_2") (pintype "passive"))
      (node (ref "LED2") (pin "2") (pinfunction "A_2") (pintype "passive"))
    )
    (net (code "62") (name "VinA") (class "Default")
      (node (ref "SSR1") (pin "5") (pinfunction "5_5") (pintype "passive"))
    )
    (net (code "63") (name "VinB") (class "Default")
      (node (ref "SSR2") (pin "5") (pinfunction "5_5") (pintype "passive"))
    )
  )
)
